# ignition5.net
KiCad netlist of a schematic drawn in EAGLE
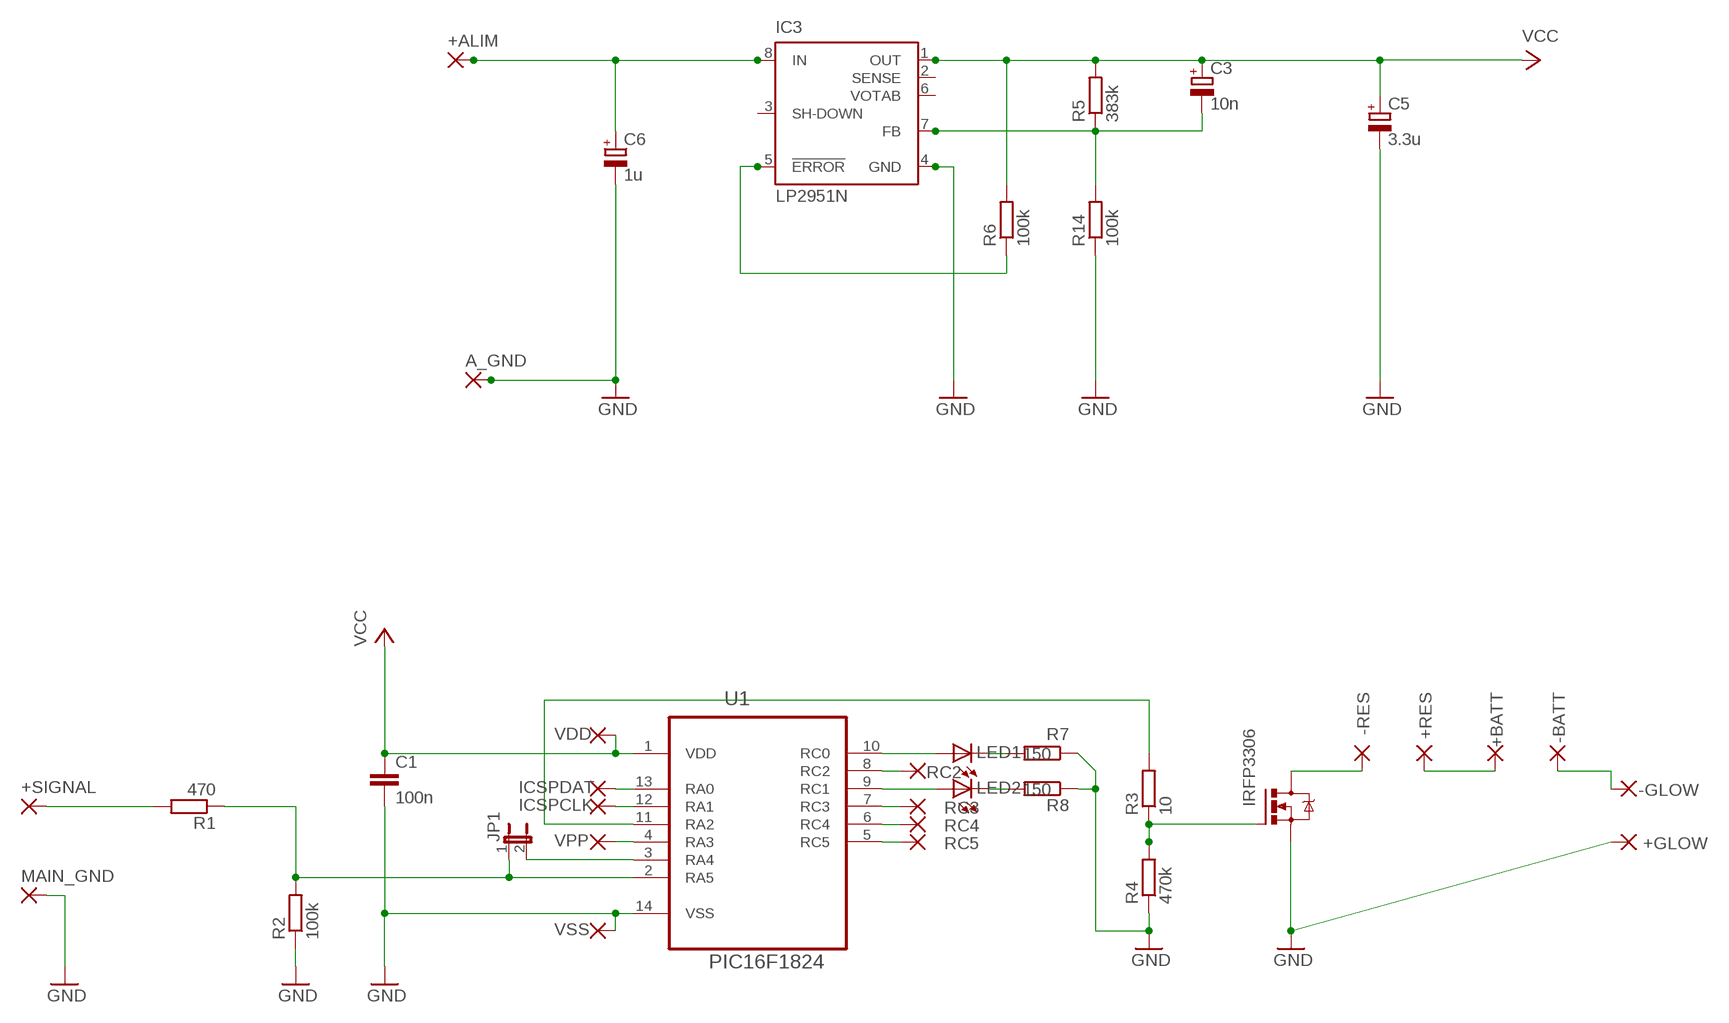
[diagram p0: schematic, sheet 1]

(export (version "E")
  (design (tool "Eeschema 10.0.6"))
  (components
    (comp (ref "+ALIM")
      (value "2,15/1,0")
      (footprint "eagle-import:2,15_1,0")
      (libsource (lib "eagle-import") (part "2,15/1,0"))
    )
    (comp (ref "+BATT")
      (value "WIREPAD3,17/1,3")
      (footprint "eagle-import:3,17_1,3")
      (libsource (lib "eagle-import") (part "WIREPAD3,17/1,3"))
    )
    (comp (ref "+GLOW")
      (value "WIREPAD3,17/1,3")
      (footprint "eagle-import:3,17_1,3")
      (libsource (lib "eagle-import") (part "WIREPAD3,17/1,3"))
    )
    (comp (ref "+RES")
      (value "WIREPAD3,17/1,3")
      (footprint "eagle-import:3,17_1,3")
      (libsource (lib "eagle-import") (part "WIREPAD3,17/1,3"))
    )
    (comp (ref "+SIGNAL")
      (value "2,15/1,0")
      (footprint "eagle-import:2,15_1,0")
      (libsource (lib "eagle-import") (part "2,15/1,0"))
    )
    (comp (ref "-BATT")
      (value "WIREPAD3,17/1,3")
      (footprint "eagle-import:3,17_1,3")
      (libsource (lib "eagle-import") (part "WIREPAD3,17/1,3"))
    )
    (comp (ref "-GLOW")
      (value "WIREPAD3,17/1,3")
      (footprint "eagle-import:3,17_1,3")
      (libsource (lib "eagle-import") (part "WIREPAD3,17/1,3"))
    )
    (comp (ref "-RES")
      (value "WIREPAD3,17/1,3")
      (footprint "eagle-import:3,17_1,3")
      (libsource (lib "eagle-import") (part "WIREPAD3,17/1,3"))
    )
    (comp (ref "A_GND")
      (value "2,15/1,0")
      (footprint "eagle-import:2,15_1,0")
      (libsource (lib "eagle-import") (part "2,15/1,0"))
    )
    (comp (ref "C1")
      (value "100n")
      (footprint "eagle-import:C050-035X075")
      (libsource (lib "eagle-import") (part "C-EU050-035X075"))
    )
    (comp (ref "C3")
      (value "10n")
      (footprint "eagle-import:E5-6")
      (libsource (lib "eagle-import") (part "CPOL-EUE5-6"))
    )
    (comp (ref "C5")
      (value "3.3u")
      (footprint "eagle-import:E2,5-5")
      (libsource (lib "eagle-import") (part "CPOL-EUE2.5-5"))
    )
    (comp (ref "C6")
      (value "1u")
      (footprint "eagle-import:E2,5-5")
      (libsource (lib "eagle-import") (part "CPOL-EUE2.5-5"))
    )
    (comp (ref "IC3")
      (value "LP2951N")
      (footprint "eagle-import:DIL08")
      (libsource (lib "eagle-import") (part "LP2951N"))
    )
    (comp (ref "ICSPCLK")
      (value "2,15/1,0")
      (footprint "eagle-import:2,15_1,0")
      (libsource (lib "eagle-import") (part "2,15/1,0"))
    )
    (comp (ref "ICSPDAT")
      (value "2,15/1,0")
      (footprint "eagle-import:2,15_1,0")
      (libsource (lib "eagle-import") (part "2,15/1,0"))
    )
    (comp (ref "JP1")
      (value "JP1E")
      (footprint "eagle-import:JP1")
      (libsource (lib "eagle-import") (part "JP1E"))
    )
    (comp (ref "LED1")
      (value "LED3MM")
      (footprint "eagle-import:LED3MM")
      (libsource (lib "eagle-import") (part "LED3MM"))
    )
    (comp (ref "LED2")
      (value "LED3MM")
      (footprint "eagle-import:LED3MM")
      (libsource (lib "eagle-import") (part "LED3MM"))
    )
    (comp (ref "MAIN_GND")
      (value "2,15/1,0")
      (footprint "eagle-import:2,15_1,0")
      (libsource (lib "eagle-import") (part "2,15/1,0"))
    )
    (comp (ref "Q2")
      (value "IRFP3306")
      (footprint "eagle-import:TO247BV")
      (libsource (lib "eagle-import") (part "IRFPC40"))
    )
    (comp (ref "R1")
      (value "470")
      (footprint "eagle-import:0207_7")
      (libsource (lib "eagle-import") (part "R-EU_0207/7"))
    )
    (comp (ref "R2")
      (value "100k")
      (footprint "eagle-import:0207_7")
      (libsource (lib "eagle-import") (part "R-EU_0207/7"))
    )
    (comp (ref "R3")
      (value "10")
      (footprint "eagle-import:0207_7")
      (libsource (lib "eagle-import") (part "R-EU_0207/7"))
    )
    (comp (ref "R4")
      (value "470k")
      (footprint "eagle-import:0207_7")
      (libsource (lib "eagle-import") (part "R-EU_0207/7"))
    )
    (comp (ref "R5")
      (value "383k")
      (footprint "eagle-import:0207_7")
      (libsource (lib "eagle-import") (part "R-EU_0207/7"))
    )
    (comp (ref "R6")
      (value "100k")
      (footprint "eagle-import:0207_7")
      (libsource (lib "eagle-import") (part "R-EU_0207/7"))
    )
    (comp (ref "R7")
      (value "150")
      (footprint "eagle-import:0207_7")
      (libsource (lib "eagle-import") (part "R-EU_0207/7"))
    )
    (comp (ref "R8")
      (value "150")
      (footprint "eagle-import:0207_7")
      (libsource (lib "eagle-import") (part "R-EU_0207/7"))
    )
    (comp (ref "R14")
      (value "100k")
      (footprint "eagle-import:0207_7")
      (libsource (lib "eagle-import") (part "R-EU_0207/7"))
    )
    (comp (ref "RC2")
      (value "2,15/1,0")
      (footprint "eagle-import:2,15_1,0")
      (libsource (lib "eagle-import") (part "2,15/1,0"))
    )
    (comp (ref "RC3")
      (value "2,15/1,0")
      (footprint "eagle-import:2,15_1,0")
      (libsource (lib "eagle-import") (part "2,15/1,0"))
    )
    (comp (ref "RC4")
      (value "2,15/1,0")
      (footprint "eagle-import:2,15_1,0")
      (libsource (lib "eagle-import") (part "2,15/1,0"))
    )
    (comp (ref "RC5")
      (value "2,15/1,0")
      (footprint "eagle-import:2,15_1,0")
      (libsource (lib "eagle-import") (part "2,15/1,0"))
    )
    (comp (ref "U1")
      (value "PIC16F1824")
      (footprint "eagle-import:DIP254P762X533-14")
      (fields (field (name "MPN") "PIC16F1824-I/P"))
      (libsource (lib "eagle-import") (part "PIC16F1824-I/P"))
    )
    (comp (ref "VDD")
      (value "WIREPAD2,15/1,0")
      (footprint "eagle-import:2,15_1,0")
      (libsource (lib "eagle-import") (part "WIREPAD2,15/1,0"))
    )
    (comp (ref "VPP")
      (value "2,15/1,0")
      (footprint "eagle-import:2,15_1,0")
      (libsource (lib "eagle-import") (part "2,15/1,0"))
    )
    (comp (ref "VSS")
      (value "WIREPAD2,15/1,0")
      (footprint "eagle-import:2,15_1,0")
      (libsource (lib "eagle-import") (part "WIREPAD2,15/1,0"))
    )
  )
  (nets
    (net (code "1") (name "GND") (class "Default")
      (node (ref "+GLOW") (pin "1") (pinfunction "P_1") (pintype "passive"))
      (node (ref "A_GND") (pin "1") (pinfunction "P_1") (pintype "passive"))
      (node (ref "C1") (pin "2") (pinfunction "2_2") (pintype "passive"))
      (node (ref "C5") (pin "-") (pinfunction "-_-") (pintype "passive"))
      (node (ref "C6") (pin "-") (pinfunction "-_-") (pintype "passive"))
      (node (ref "IC3") (pin "4") (pinfunction "GND_4") (pintype "power_in"))
      (node (ref "MAIN_GND") (pin "1") (pinfunction "P_1") (pintype "passive"))
      (node (ref "Q2") (pin "S") (pinfunction "S_S") (pintype "passive"))
      (node (ref "R14") (pin "1") (pinfunction "1_1") (pintype "passive"))
      (node (ref "R2") (pin "1") (pinfunction "1_1") (pintype "passive"))
      (node (ref "R4") (pin "1") (pinfunction "1_1") (pintype "passive"))
      (node (ref "R7") (pin "1") (pinfunction "1_1") (pintype "passive"))
      (node (ref "R8") (pin "1") (pinfunction "1_1") (pintype "passive"))
      (node (ref "U1") (pin "14") (pinfunction "VSS_14") (pintype "power_in"))
      (node (ref "VSS") (pin "1") (pinfunction "P_1") (pintype "passive"))
    )
    (net (code "2") (name "Net-(+ALIM-P)") (class "Default")
      (node (ref "+ALIM") (pin "1") (pinfunction "P_1") (pintype "passive"))
      (node (ref "C6") (pin "+") (pinfunction "+_+") (pintype "passive"))
      (node (ref "IC3") (pin "8") (pinfunction "IN_8") (pintype "input"))
    )
    (net (code "3") (name "Net-(+BATT-P)") (class "Default")
      (node (ref "+BATT") (pin "1") (pinfunction "P_1") (pintype "passive"))
      (node (ref "+RES") (pin "1") (pinfunction "P_1") (pintype "passive"))
    )
    (net (code "4") (name "Net-(+SIGNAL-P)") (class "Default")
      (node (ref "+SIGNAL") (pin "1") (pinfunction "P_1") (pintype "passive"))
      (node (ref "R1") (pin "2") (pinfunction "2_2") (pintype "passive"))
    )
    (net (code "5") (name "Net-(-BATT-P)") (class "Default")
      (node (ref "-BATT") (pin "1") (pinfunction "P_1") (pintype "passive"))
      (node (ref "-GLOW") (pin "1") (pinfunction "P_1") (pintype "passive"))
    )
    (net (code "6") (name "Net-(-RES-P)") (class "Default")
      (node (ref "-RES") (pin "1") (pinfunction "P_1") (pintype "passive"))
      (node (ref "Q2") (pin "D") (pinfunction "D_D") (pintype "passive"))
    )
    (net (code "7") (name "Net-(IC3-FB)") (class "Default")
      (node (ref "C3") (pin "-") (pinfunction "-_-") (pintype "passive"))
      (node (ref "IC3") (pin "7") (pinfunction "FB_7") (pintype "input"))
      (node (ref "R14") (pin "2") (pinfunction "2_2") (pintype "passive"))
      (node (ref "R5") (pin "1") (pinfunction "1_1") (pintype "passive"))
    )
    (net (code "8") (name "Net-(IC3-~{ERROR})") (class "Default")
      (node (ref "IC3") (pin "5") (pinfunction "~{ERROR}_5") (pintype "output"))
      (node (ref "R6") (pin "1") (pinfunction "1_1") (pintype "passive"))
    )
    (net (code "9") (name "Net-(ICSPCLK-P)") (class "Default")
      (node (ref "ICSPCLK") (pin "1") (pinfunction "P_1") (pintype "passive"))
      (node (ref "U1") (pin "12") (pinfunction "RA1_12") (pintype "bidirectional"))
    )
    (net (code "10") (name "Net-(ICSPDAT-P)") (class "Default")
      (node (ref "ICSPDAT") (pin "1") (pinfunction "P_1") (pintype "passive"))
      (node (ref "U1") (pin "13") (pinfunction "RA0_13") (pintype "bidirectional"))
    )
    (net (code "11") (name "Net-(LED1-C)") (class "Default")
      (node (ref "LED1") (pin "K") (pinfunction "C_K") (pintype "passive"))
      (node (ref "R7") (pin "2") (pinfunction "2_2") (pintype "passive"))
    )
    (net (code "12") (name "Net-(LED2-C)") (class "Default")
      (node (ref "LED2") (pin "K") (pinfunction "C_K") (pintype "passive"))
      (node (ref "R8") (pin "2") (pinfunction "2_2") (pintype "passive"))
    )
    (net (code "13") (name "Net-(Q2-PadG)") (class "Default")
      (node (ref "Q2") (pin "G") (pinfunction "G_G") (pintype "passive"))
      (node (ref "R3") (pin "1") (pinfunction "1_1") (pintype "passive"))
      (node (ref "R4") (pin "2") (pinfunction "2_2") (pintype "passive"))
    )
    (net (code "14") (name "Net-(RC2-P)") (class "Default")
      (node (ref "RC2") (pin "1") (pinfunction "P_1") (pintype "passive"))
      (node (ref "U1") (pin "8") (pinfunction "RC2_8") (pintype "bidirectional"))
    )
    (net (code "15") (name "Net-(RC3-P)") (class "Default")
      (node (ref "RC3") (pin "1") (pinfunction "P_1") (pintype "passive"))
      (node (ref "U1") (pin "7") (pinfunction "RC3_7") (pintype "bidirectional"))
    )
    (net (code "16") (name "Net-(RC4-P)") (class "Default")
      (node (ref "RC4") (pin "1") (pinfunction "P_1") (pintype "passive"))
      (node (ref "U1") (pin "6") (pinfunction "RC4_6") (pintype "bidirectional"))
    )
    (net (code "17") (name "Net-(RC5-P)") (class "Default")
      (node (ref "RC5") (pin "1") (pinfunction "P_1") (pintype "passive"))
      (node (ref "U1") (pin "5") (pinfunction "RC5_5") (pintype "bidirectional"))
    )
    (net (code "18") (name "Net-(U1-RA2)") (class "Default")
      (node (ref "R3") (pin "2") (pinfunction "2_2") (pintype "passive"))
      (node (ref "U1") (pin "11") (pinfunction "RA2_11") (pintype "bidirectional"))
    )
    (net (code "19") (name "Net-(U1-RA3)") (class "Default")
      (node (ref "U1") (pin "4") (pinfunction "RA3_4") (pintype "input"))
      (node (ref "VPP") (pin "1") (pinfunction "P_1") (pintype "passive"))
    )
    (net (code "20") (name "Net-(U1-RA4)") (class "Default")
      (node (ref "JP1") (pin "2") (pinfunction "2_2") (pintype "passive"))
      (node (ref "U1") (pin "3") (pinfunction "RA4_3") (pintype "bidirectional"))
    )
    (net (code "21") (name "Net-(U1-RA5)") (class "Default")
      (node (ref "JP1") (pin "1") (pinfunction "1_1") (pintype "passive"))
      (node (ref "R1") (pin "1") (pinfunction "1_1") (pintype "passive"))
      (node (ref "R2") (pin "2") (pinfunction "2_2") (pintype "passive"))
      (node (ref "U1") (pin "2") (pinfunction "RA5_2") (pintype "bidirectional"))
    )
    (net (code "22") (name "Net-(U1-RC0)") (class "Default")
      (node (ref "LED1") (pin "A") (pinfunction "A_A") (pintype "passive"))
      (node (ref "U1") (pin "10") (pinfunction "RC0_10") (pintype "bidirectional"))
    )
    (net (code "23") (name "Net-(U1-RC1)") (class "Default")
      (node (ref "LED2") (pin "A") (pinfunction "A_A") (pintype "passive"))
      (node (ref "U1") (pin "9") (pinfunction "RC1_9") (pintype "bidirectional"))
    )
    (net (code "24") (name "VCC") (class "Default")
      (node (ref "C1") (pin "1") (pinfunction "1_1") (pintype "passive"))
      (node (ref "C3") (pin "+") (pinfunction "+_+") (pintype "passive"))
      (node (ref "C5") (pin "+") (pinfunction "+_+") (pintype "passive"))
      (node (ref "IC3") (pin "1") (pinfunction "OUT_1") (pintype "input"))
      (node (ref "R5") (pin "2") (pinfunction "2_2") (pintype "passive"))
      (node (ref "R6") (pin "2") (pinfunction "2_2") (pintype "passive"))
      (node (ref "U1") (pin "1") (pinfunction "VDD_1") (pintype "power_in"))
      (node (ref "VDD") (pin "1") (pinfunction "P_1") (pintype "passive"))
    )
    (net (code "25") (name "unconnected-(IC3-SENSE-Pad2)") (class "Default")
      (node (ref "IC3") (pin "2") (pinfunction "SENSE_2") (pintype "input"))
    )
    (net (code "26") (name "unconnected-(IC3-SH-DOWN-Pad3)") (class "Default")
      (node (ref "IC3") (pin "3") (pinfunction "SH-DOWN_3") (pintype "input"))
    )
    (net (code "27") (name "unconnected-(IC3-VOTAB-Pad6)") (class "Default")
      (node (ref "IC3") (pin "6") (pinfunction "VOTAB_6") (pintype "passive"))
    )
  )
)
